# Models.net
KiCad netlist of a schematic drawn in Altium Designer
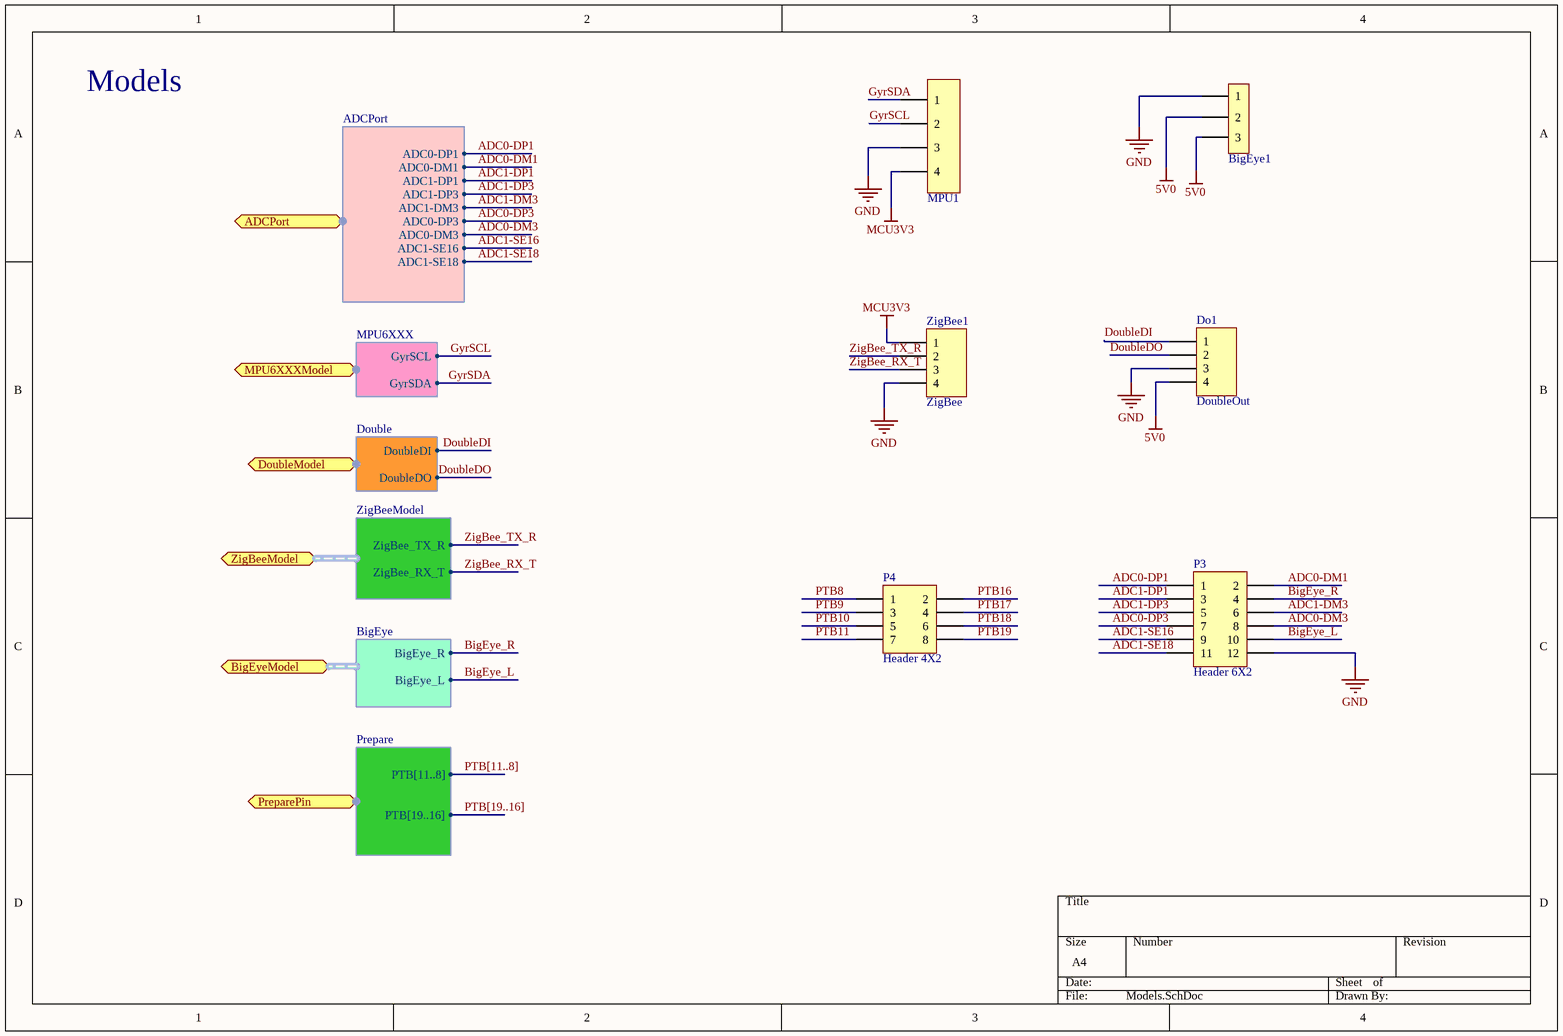
[diagram p0: Models.SchDoc]

(export (version "E")
  (design (tool "Eeschema 10.0.6"))
  (components
    (comp (ref "BigEye1") (value "Header3") (footprint "Header3") (libsource (lib "常用原件库") (part "Header3")))
    (comp (ref "Do1")
      (value "DoubleOut")
      (footprint "HDR1X4")
      (description "Header, 4-Pin")
      (fields (field (name "PUBLISHER") "Altium Limited"))
      (libsource (lib "Miscellaneous Connectors") (part "Header 4"))
    )
    (comp (ref "MPU1") (value "Header4") (footprint "Header4") (libsource (lib "常用原件库") (part "Header4")))
    (comp (ref "P3")
      (value "Header 6X2")
      (footprint "HDR2X6")
      (description "Header, 6-Pin, Dual row")
      (fields (field (name "PUBLISHER") "Altium Limited"))
      (libsource (lib "Miscellaneous Connectors") (part "Header 6X2"))
    )
    (comp (ref "P4")
      (value "Header 4X2")
      (footprint "HDR2X4")
      (description "Header, 4-Pin, Dual row")
      (fields (field (name "PUBLISHER") "Altium Limited"))
      (libsource (lib "Miscellaneous Connectors") (part "Header 4X2"))
    )
    (comp (ref "ZigBee1")
      (value "ZigBee")
      (footprint "HDR1X4")
      (description "Header, 4-Pin")
      (fields (field (name "PUBLISHER") "Altium Limited"))
      (libsource (lib "Miscellaneous Connectors") (part "Header 4"))
    )
  )
  (nets
    (net (code "7") (name "/ADC0-DM1") (class "Default")
      (node (ref "P3") (pin "2") (pinfunction "2_2") (pintype "passive"))
    )
    (net (code "8") (name "/ADC0-DM3") (class "Default")
      (node (ref "P3") (pin "8") (pinfunction "8_8") (pintype "passive"))
    )
    (net (code "9") (name "/ADC0-DP1") (class "Default")
      (node (ref "P3") (pin "1") (pinfunction "1_1") (pintype "passive"))
    )
    (net (code "10") (name "/ADC0-DP3") (class "Default")
      (node (ref "P3") (pin "7") (pinfunction "7_7") (pintype "passive"))
    )
    (net (code "11") (name "/ADC1-DM3") (class "Default")
      (node (ref "P3") (pin "6") (pinfunction "6_6") (pintype "passive"))
    )
    (net (code "12") (name "/ADC1-DP1") (class "Default")
      (node (ref "P3") (pin "3") (pinfunction "3_3") (pintype "passive"))
    )
    (net (code "13") (name "/ADC1-DP3") (class "Default")
      (node (ref "P3") (pin "5") (pinfunction "5_5") (pintype "passive"))
    )
    (net (code "14") (name "/ADC1-SE16") (class "Default")
      (node (ref "P3") (pin "9") (pinfunction "9_9") (pintype "passive"))
    )
    (net (code "15") (name "/ADC1-SE18") (class "Default")
      (node (ref "P3") (pin "11") (pinfunction "11_11") (pintype "passive"))
    )
    (net (code "16") (name "/BigEye_L") (class "Default")
      (node (ref "P3") (pin "10") (pinfunction "10_10") (pintype "passive"))
    )
    (net (code "17") (name "/BigEye_R") (class "Default")
      (node (ref "P3") (pin "4") (pinfunction "4_4") (pintype "passive"))
    )
    (net (code "18") (name "/DoubleDI") (class "Default")
      (node (ref "Do1") (pin "1") (pinfunction "1_1") (pintype "passive"))
    )
    (net (code "19") (name "/DoubleDO") (class "Default")
      (node (ref "Do1") (pin "2") (pinfunction "2_2") (pintype "passive"))
    )
    (net (code "20") (name "/GyrSCL") (class "Default")
      (node (ref "MPU1") (pin "2") (pinfunction "2_2") (pintype "passive"))
    )
    (net (code "21") (name "/GyrSDA") (class "Default")
      (node (ref "MPU1") (pin "1") (pinfunction "1_1") (pintype "passive"))
    )
    (net (code "22") (name "/PTB8") (class "Default")
      (node (ref "P4") (pin "1") (pinfunction "1_1") (pintype "passive"))
    )
    (net (code "23") (name "/PTB9") (class "Default")
      (node (ref "P4") (pin "3") (pinfunction "3_3") (pintype "passive"))
    )
    (net (code "24") (name "/PTB10") (class "Default")
      (node (ref "P4") (pin "5") (pinfunction "5_5") (pintype "passive"))
    )
    (net (code "25") (name "/PTB11") (class "Default")
      (node (ref "P4") (pin "7") (pinfunction "7_7") (pintype "passive"))
    )
    (net (code "26") (name "/PTB16") (class "Default")
      (node (ref "P4") (pin "2") (pinfunction "2_2") (pintype "passive"))
    )
    (net (code "27") (name "/PTB17") (class "Default")
      (node (ref "P4") (pin "4") (pinfunction "4_4") (pintype "passive"))
    )
    (net (code "28") (name "/PTB18") (class "Default")
      (node (ref "P4") (pin "6") (pinfunction "6_6") (pintype "passive"))
    )
    (net (code "29") (name "/PTB19") (class "Default")
      (node (ref "P4") (pin "8") (pinfunction "8_8") (pintype "passive"))
    )
    (net (code "32") (name "/ZigBee_RX_T") (class "Default")
      (node (ref "ZigBee1") (pin "3") (pinfunction "3_3") (pintype "passive"))
    )
    (net (code "33") (name "/ZigBee_TX_R") (class "Default")
      (node (ref "ZigBee1") (pin "2") (pinfunction "2_2") (pintype "passive"))
    )
    (net (code "40") (name "5V0") (class "Default")
      (node (ref "BigEye1") (pin "2") (pinfunction "2_2") (pintype "passive"))
      (node (ref "BigEye1") (pin "3") (pinfunction "3_3") (pintype "passive"))
      (node (ref "Do1") (pin "4") (pinfunction "4_4") (pintype "passive"))
    )
    (net (code "41") (name "GND") (class "Default")
      (node (ref "BigEye1") (pin "1") (pinfunction "1_1") (pintype "passive"))
      (node (ref "Do1") (pin "3") (pinfunction "3_3") (pintype "passive"))
      (node (ref "MPU1") (pin "3") (pinfunction "3_3") (pintype "passive"))
      (node (ref "P3") (pin "12") (pinfunction "12_12") (pintype "passive"))
      (node (ref "ZigBee1") (pin "4") (pinfunction "4_4") (pintype "passive"))
    )
    (net (code "42") (name "MCU3V3") (class "Default")
      (node (ref "MPU1") (pin "4") (pinfunction "4_4") (pintype "passive"))
      (node (ref "ZigBee1") (pin "1") (pinfunction "1_1") (pintype "passive"))
    )
  )
)
